# DM3370_Connector_C.net
KiCad netlist of a schematic drawn in Altium Designer
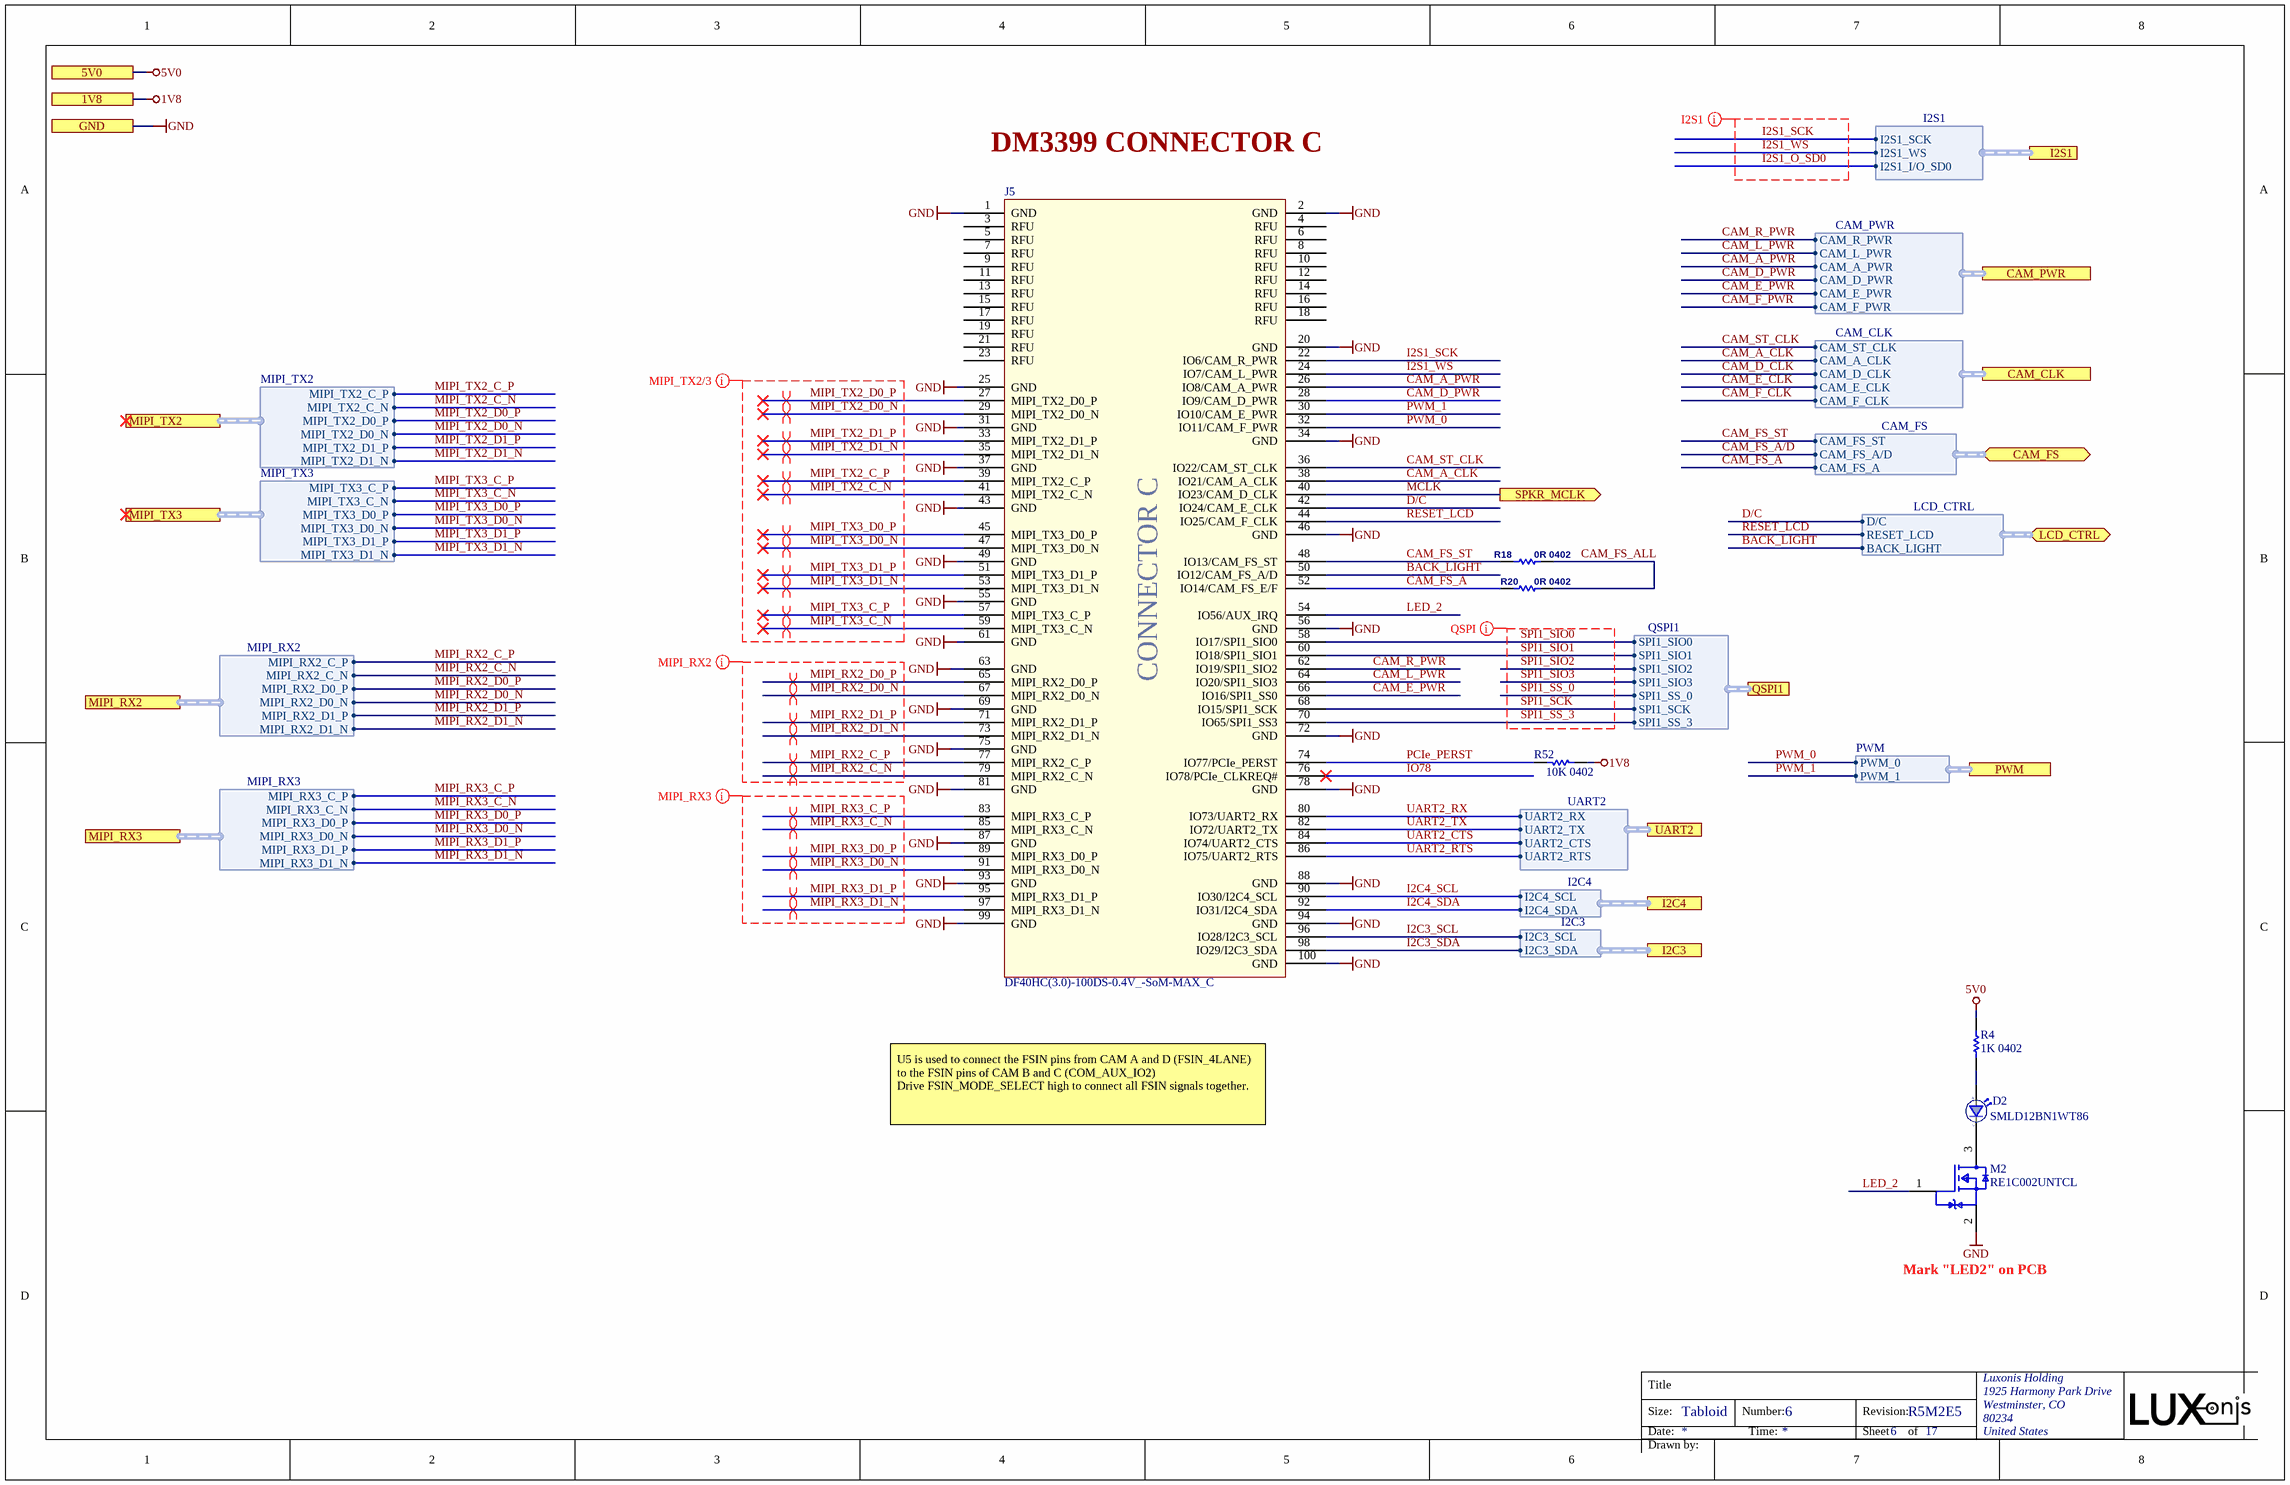
[diagram p0: DM3370_Connector_C.SchDoc]

(export (version "E")
  (design (tool "Eeschema 10.0.6"))
  (components
    (comp (ref "D2")
      (value "CMP-008-000009-2")
      (footprint "SML_D1xx8W")
      (description "LED Uni-Color Blue 2-Pin Chip 0603(1608Metric) T/R")
      (fields (field (name "MANUFACTURER PART NUMBER 1") "SMLD12BN1WT86"))
      (libsource (lib "Luxonis LLC") (part "SML-D12BN1WT86"))
    )
    (comp (ref "J5")
      (value "DF40HC(3.0)-100DS-0.4V_-SoM-MAX_C")
      (footprint "SOM_MAX_CONN_C_DF40HC-3.0-100DS-0.4V_minpad")
      (description "OAK-SoM-MAX base board conn. C")
      (fields (field (name "SOURCE") "LuxonisMaster_nejc.SchLib"))
      (libsource (lib "Luxonis LLC") (part "DF40HC(3.0)-100DS-0.4V_-SoM-MAX_C"))
    )
    (comp (ref "M2")
      (value "RE1C002UNTCL")
      (footprint "LuxonisMaster:RE1C002UNTCL")
      (description "MOSFET N-CH 20V 0.2A EMT3")
      (libsource (lib "LuxonisMaster") (part "RE1C002UNTCL"))
    )
    (comp (ref "R4")
      (value "1K 0402")
      (footprint "RES_Altium_Vault_Generic:RESC0402(1005)_L")
      (fields (field (name "TOLERANCE") "1%"))
      (libsource (lib "LuxonisMaster") (part "RC0402FR-071KL"))
    )
    (comp (ref "R18")
      (value "0R 0402")
      (footprint "RES_Altium_Vault_Generic:RESC0402(1005)_L")
      (description "RES SMD 0 OHM JUMPER 1/16W 0402")
      (fields (field (name "TOLERANCE") "5%"))
      (libsource (lib "LuxonisMaster") (part "CRCW04020000Z0ED"))
    )
    (comp (ref "R20")
      (value "0R 0402")
      (footprint "RES_Altium_Vault_Generic:RESC0402(1005)_L")
      (description "RES SMD 0 OHM JUMPER 1/16W 0402")
      (fields (field (name "TOLERANCE") "5%"))
      (libsource (lib "LuxonisMaster") (part "CRCW04020000Z0ED"))
    )
    (comp (ref "R52")
      (value "10K 0402")
      (footprint "RES_Altium_Vault_Generic:RESC0402(1005)_L")
      (fields (field (name "TOLERANCE") "1%"))
      (libsource (lib "LuxonisMaster") (part "RC0402FR-1310KL"))
    )
  )
  (nets
    (net (code "15") (name "/BACK_LIGHT") (class "Default")
      (node (ref "J5") (pin "50") (pinfunction "IO12/CAM_FS_A/D_50") (pintype "passive"))
    )
    (net (code "16") (name "/CAM_A_CLK") (class "Default")
      (node (ref "J5") (pin "38") (pinfunction "IO21/CAM_A_CLK_38") (pintype "passive"))
    )
    (net (code "17") (name "/CAM_A_PWR") (class "Default")
      (node (ref "J5") (pin "26") (pinfunction "IO8/CAM_A_PWR_26") (pintype "passive"))
    )
    (net (code "19") (name "/CAM_D_PWR") (class "Default")
      (node (ref "J5") (pin "28") (pinfunction "IO9/CAM_D_PWR_28") (pintype "passive"))
    )
    (net (code "21") (name "/CAM_E_PWR") (class "Default")
      (node (ref "J5") (pin "66") (pinfunction "IO16/SPI1_SS0_66") (pintype "passive"))
    )
    (net (code "22") (name "/CAM_FS_A") (class "Default")
      (node (ref "J5") (pin "52") (pinfunction "IO14/CAM_FS_E/F_52") (pintype "passive"))
      (node (ref "R20") (pin "2") (pinfunction "2_2") (pintype "passive"))
    )
    (net (code "23") (name "/CAM_FS_ALL") (class "Default")
      (node (ref "R18") (pin "1") (pinfunction "1_1") (pintype "passive"))
      (node (ref "R20") (pin "1") (pinfunction "1_1") (pintype "passive"))
    )
    (net (code "25") (name "/CAM_FS_ST") (class "Default")
      (node (ref "J5") (pin "48") (pinfunction "IO13/CAM_FS_ST_48") (pintype "passive"))
      (node (ref "R18") (pin "2") (pinfunction "2_2") (pintype "passive"))
    )
    (net (code "28") (name "/CAM_L_PWR") (class "Default")
      (node (ref "J5") (pin "64") (pinfunction "IO20/SPI1_SIO3_64") (pintype "passive"))
    )
    (net (code "29") (name "/CAM_R_PWR") (class "Default")
      (node (ref "J5") (pin "62") (pinfunction "IO19/SPI1_SIO2_62") (pintype "passive"))
    )
    (net (code "30") (name "/CAM_ST_CLK") (class "Default")
      (node (ref "J5") (pin "36") (pinfunction "IO22/CAM_ST_CLK_36") (pintype "passive"))
    )
    (net (code "31") (name "/D{slash}C") (class "Default")
      (node (ref "J5") (pin "42") (pinfunction "IO24/CAM_E_CLK_42") (pintype "passive"))
    )
    (net (code "32") (name "/I2C3_SCL") (class "Default")
      (node (ref "J5") (pin "96") (pinfunction "IO28/I2C3_SCL_96") (pintype "passive"))
    )
    (net (code "33") (name "/I2C3_SDA") (class "Default")
      (node (ref "J5") (pin "98") (pinfunction "IO29/I2C3_SDA_98") (pintype "passive"))
    )
    (net (code "34") (name "/I2C4_SCL") (class "Default")
      (node (ref "J5") (pin "90") (pinfunction "IO30/I2C4_SCL_90") (pintype "passive"))
    )
    (net (code "35") (name "/I2C4_SDA") (class "Default")
      (node (ref "J5") (pin "92") (pinfunction "IO31/I2C4_SDA_92") (pintype "passive"))
    )
    (net (code "37") (name "/I2S1_SCK") (class "Default")
      (node (ref "J5") (pin "22") (pinfunction "IO6/CAM_R_PWR_22") (pintype "passive"))
    )
    (net (code "38") (name "/I2S1_WS") (class "Default")
      (node (ref "J5") (pin "24") (pinfunction "IO7/CAM_L_PWR_24") (pintype "passive"))
    )
    (net (code "39") (name "/IO78") (class "Default")
      (node (ref "J5") (pin "76") (pinfunction "IO78/PCIe_CLKREQ#_76") (pintype "passive+no_connect"))
    )
    (net (code "40") (name "/LED_2") (class "Default")
      (node (ref "J5") (pin "54") (pinfunction "IO56/AUX_IRQ_54") (pintype "passive"))
      (node (ref "M2") (pin "1") (pinfunction "Gate_1") (pintype "passive"))
    )
    (net (code "41") (name "/MCLK") (class "Default")
      (node (ref "J5") (pin "40") (pinfunction "IO23/CAM_D_CLK_40") (pintype "passive"))
    )
    (net (code "42") (name "/MIPI_RX2_C_N") (class "Default")
      (node (ref "J5") (pin "79") (pinfunction "MIPI_RX2_C_N_79") (pintype "passive"))
    )
    (net (code "43") (name "/MIPI_RX2_C_P") (class "Default")
      (node (ref "J5") (pin "77") (pinfunction "MIPI_RX2_C_P_77") (pintype "passive"))
    )
    (net (code "44") (name "/MIPI_RX2_D0_N") (class "Default")
      (node (ref "J5") (pin "67") (pinfunction "MIPI_RX2_D0_N_67") (pintype "passive"))
    )
    (net (code "45") (name "/MIPI_RX2_D0_P") (class "Default")
      (node (ref "J5") (pin "65") (pinfunction "MIPI_RX2_D0_P_65") (pintype "passive"))
    )
    (net (code "46") (name "/MIPI_RX2_D1_N") (class "Default")
      (node (ref "J5") (pin "73") (pinfunction "MIPI_RX2_D1_N_73") (pintype "passive"))
    )
    (net (code "47") (name "/MIPI_RX2_D1_P") (class "Default")
      (node (ref "J5") (pin "71") (pinfunction "MIPI_RX2_D1_P_71") (pintype "passive"))
    )
    (net (code "48") (name "/MIPI_RX3_C_N") (class "Default")
      (node (ref "J5") (pin "85") (pinfunction "MIPI_RX3_C_N_85") (pintype "passive"))
    )
    (net (code "49") (name "/MIPI_RX3_C_P") (class "Default")
      (node (ref "J5") (pin "83") (pinfunction "MIPI_RX3_C_P_83") (pintype "passive"))
    )
    (net (code "50") (name "/MIPI_RX3_D0_N") (class "Default")
      (node (ref "J5") (pin "91") (pinfunction "MIPI_RX3_D0_N_91") (pintype "passive"))
    )
    (net (code "51") (name "/MIPI_RX3_D0_P") (class "Default")
      (node (ref "J5") (pin "89") (pinfunction "MIPI_RX3_D0_P_89") (pintype "passive"))
    )
    (net (code "52") (name "/MIPI_RX3_D1_N") (class "Default")
      (node (ref "J5") (pin "97") (pinfunction "MIPI_RX3_D1_N_97") (pintype "passive"))
    )
    (net (code "53") (name "/MIPI_RX3_D1_P") (class "Default")
      (node (ref "J5") (pin "95") (pinfunction "MIPI_RX3_D1_P_95") (pintype "passive"))
    )
    (net (code "54") (name "/MIPI_TX2_C_N") (class "Default")
      (node (ref "J5") (pin "41") (pinfunction "MIPI_TX2_C_N_41") (pintype "passive+no_connect"))
    )
    (net (code "55") (name "/MIPI_TX2_C_P") (class "Default")
      (node (ref "J5") (pin "39") (pinfunction "MIPI_TX2_C_P_39") (pintype "passive+no_connect"))
    )
    (net (code "56") (name "/MIPI_TX2_D0_N") (class "Default")
      (node (ref "J5") (pin "29") (pinfunction "MIPI_TX2_D0_N_29") (pintype "passive+no_connect"))
    )
    (net (code "57") (name "/MIPI_TX2_D0_P") (class "Default")
      (node (ref "J5") (pin "27") (pinfunction "MIPI_TX2_D0_P_27") (pintype "passive"))
    )
    (net (code "58") (name "/MIPI_TX2_D1_N") (class "Default")
      (node (ref "J5") (pin "35") (pinfunction "MIPI_TX2_D1_N_35") (pintype "passive"))
    )
    (net (code "59") (name "/MIPI_TX2_D1_P") (class "Default")
      (node (ref "J5") (pin "33") (pinfunction "MIPI_TX2_D1_P_33") (pintype "passive"))
    )
    (net (code "60") (name "/MIPI_TX3_C_N") (class "Default")
      (node (ref "J5") (pin "59") (pinfunction "MIPI_TX3_C_N_59") (pintype "passive"))
    )
    (net (code "61") (name "/MIPI_TX3_C_P") (class "Default")
      (node (ref "J5") (pin "57") (pinfunction "MIPI_TX3_C_P_57") (pintype "passive"))
    )
    (net (code "62") (name "/MIPI_TX3_D0_N") (class "Default")
      (node (ref "J5") (pin "47") (pinfunction "MIPI_TX3_D0_N_47") (pintype "passive"))
    )
    (net (code "63") (name "/MIPI_TX3_D0_P") (class "Default")
      (node (ref "J5") (pin "45") (pinfunction "MIPI_TX3_D0_P_45") (pintype "passive"))
    )
    (net (code "64") (name "/MIPI_TX3_D1_N") (class "Default")
      (node (ref "J5") (pin "53") (pinfunction "MIPI_TX3_D1_N_53") (pintype "passive"))
    )
    (net (code "65") (name "/MIPI_TX3_D1_P") (class "Default")
      (node (ref "J5") (pin "51") (pinfunction "MIPI_TX3_D1_P_51") (pintype "passive"))
    )
    (net (code "66") (name "/PCIe_PERST") (class "Default")
      (node (ref "J5") (pin "74") (pinfunction "IO77/PCIe_PERST_74") (pintype "passive"))
      (node (ref "R52") (pin "2") (pinfunction "2_2") (pintype "passive"))
    )
    (net (code "67") (name "/PWM_0") (class "Default")
      (node (ref "J5") (pin "32") (pinfunction "IO11/CAM_F_PWR_32") (pintype "passive"))
    )
    (net (code "68") (name "/PWM_1") (class "Default")
      (node (ref "J5") (pin "30") (pinfunction "IO10/CAM_E_PWR_30") (pintype "passive"))
    )
    (net (code "69") (name "/RESET_LCD") (class "Default")
      (node (ref "J5") (pin "44") (pinfunction "IO25/CAM_F_CLK_44") (pintype "passive"))
    )
    (net (code "70") (name "/SPI1_SCK") (class "Default")
      (node (ref "J5") (pin "68") (pinfunction "IO15/SPI1_SCK_68") (pintype "passive"))
    )
    (net (code "71") (name "/SPI1_SIO0") (class "Default")
      (node (ref "J5") (pin "58") (pinfunction "IO17/SPI1_SIO0_58") (pintype "passive"))
    )
    (net (code "72") (name "/SPI1_SIO1") (class "Default")
      (node (ref "J5") (pin "60") (pinfunction "IO18/SPI1_SIO1_60") (pintype "passive"))
    )
    (net (code "76") (name "/SPI1_SS_3") (class "Default")
      (node (ref "J5") (pin "70") (pinfunction "IO65/SPI1_SS3_70") (pintype "passive"))
    )
    (net (code "77") (name "/UART2_CTS") (class "Default")
      (node (ref "J5") (pin "84") (pinfunction "IO74/UART2_CTS_84") (pintype "passive"))
    )
    (net (code "78") (name "/UART2_RTS") (class "Default")
      (node (ref "J5") (pin "86") (pinfunction "IO75/UART2_RTS_86") (pintype "passive"))
    )
    (net (code "79") (name "/UART2_RX") (class "Default")
      (node (ref "J5") (pin "80") (pinfunction "IO73/UART2_RX_80") (pintype "passive"))
    )
    (net (code "80") (name "/UART2_TX") (class "Default")
      (node (ref "J5") (pin "82") (pinfunction "IO72/UART2_TX_82") (pintype "passive"))
    )
    (net (code "95") (name "1V8") (class "Default")
      (node (ref "R52") (pin "1") (pinfunction "1_1") (pintype "passive"))
    )
    (net (code "96") (name "5V0") (class "Default")
      (node (ref "R4") (pin "2") (pinfunction "2_2") (pintype "passive"))
    )
    (net (code "97") (name "GND") (class "Default")
      (node (ref "J5") (pin "1") (pinfunction "GND_1") (pintype "passive"))
      (node (ref "J5") (pin "100") (pinfunction "GND_100") (pintype "passive"))
      (node (ref "J5") (pin "2") (pinfunction "GND_2") (pintype "passive"))
      (node (ref "J5") (pin "20") (pinfunction "GND_20") (pintype "passive"))
      (node (ref "J5") (pin "25") (pinfunction "GND_25") (pintype "passive"))
      (node (ref "J5") (pin "31") (pinfunction "GND_31") (pintype "passive"))
      (node (ref "J5") (pin "34") (pinfunction "GND_34") (pintype "passive"))
      (node (ref "J5") (pin "37") (pinfunction "GND_37") (pintype "passive"))
      (node (ref "J5") (pin "43") (pinfunction "GND_43") (pintype "passive"))
      (node (ref "J5") (pin "46") (pinfunction "GND_46") (pintype "passive"))
      (node (ref "J5") (pin "49") (pinfunction "GND_49") (pintype "passive"))
      (node (ref "J5") (pin "55") (pinfunction "GND_55") (pintype "passive"))
      (node (ref "J5") (pin "56") (pinfunction "GND_56") (pintype "passive"))
      (node (ref "J5") (pin "61") (pinfunction "GND_61") (pintype "passive"))
      (node (ref "J5") (pin "63") (pinfunction "GND_63") (pintype "passive"))
      (node (ref "J5") (pin "69") (pinfunction "GND_69") (pintype "passive"))
      (node (ref "J5") (pin "72") (pinfunction "GND_72") (pintype "passive"))
      (node (ref "J5") (pin "75") (pinfunction "GND_75") (pintype "passive"))
      (node (ref "J5") (pin "78") (pinfunction "GND_78") (pintype "passive"))
      (node (ref "J5") (pin "81") (pinfunction "GND_81") (pintype "passive"))
      (node (ref "J5") (pin "87") (pinfunction "GND_87") (pintype "passive"))
      (node (ref "J5") (pin "88") (pinfunction "GND_88") (pintype "passive"))
      (node (ref "J5") (pin "93") (pinfunction "GND_93") (pintype "passive"))
      (node (ref "J5") (pin "94") (pinfunction "GND_94") (pintype "passive"))
      (node (ref "J5") (pin "99") (pinfunction "GND_99") (pintype "passive"))
      (node (ref "M2") (pin "2") (pinfunction "Source_2") (pintype "passive"))
    )
    (net (code "98") (name "Net-(D2-A)") (class "Default")
      (node (ref "D2") (pin "2") (pinfunction "A_2") (pintype "passive"))
      (node (ref "R4") (pin "1") (pinfunction "1_1") (pintype "passive"))
    )
    (net (code "99") (name "Net-(D2-C)") (class "Default")
      (node (ref "D2") (pin "1") (pinfunction "C_1") (pintype "passive"))
      (node (ref "M2") (pin "3") (pinfunction "Drain_3") (pintype "passive"))
    )
    (net (code "100") (name "unconnected-(J5-RFU-Pad3)") (class "Default")
      (node (ref "J5") (pin "3") (pinfunction "RFU_3") (pintype "passive"))
    )
    (net (code "101") (name "unconnected-(J5-RFU-Pad4)") (class "Default")
      (node (ref "J5") (pin "4") (pinfunction "RFU_4") (pintype "passive"))
    )
    (net (code "102") (name "unconnected-(J5-RFU-Pad5)") (class "Default")
      (node (ref "J5") (pin "5") (pinfunction "RFU_5") (pintype "passive"))
    )
    (net (code "103") (name "unconnected-(J5-RFU-Pad6)") (class "Default")
      (node (ref "J5") (pin "6") (pinfunction "RFU_6") (pintype "passive"))
    )
    (net (code "104") (name "unconnected-(J5-RFU-Pad7)") (class "Default")
      (node (ref "J5") (pin "7") (pinfunction "RFU_7") (pintype "passive"))
    )
    (net (code "105") (name "unconnected-(J5-RFU-Pad8)") (class "Default")
      (node (ref "J5") (pin "8") (pinfunction "RFU_8") (pintype "passive"))
    )
    (net (code "106") (name "unconnected-(J5-RFU-Pad9)") (class "Default")
      (node (ref "J5") (pin "9") (pinfunction "RFU_9") (pintype "passive"))
    )
    (net (code "107") (name "unconnected-(J5-RFU-Pad10)") (class "Default")
      (node (ref "J5") (pin "10") (pinfunction "RFU_10") (pintype "passive"))
    )
    (net (code "108") (name "unconnected-(J5-RFU-Pad11)") (class "Default")
      (node (ref "J5") (pin "11") (pinfunction "RFU_11") (pintype "passive"))
    )
    (net (code "109") (name "unconnected-(J5-RFU-Pad12)") (class "Default")
      (node (ref "J5") (pin "12") (pinfunction "RFU_12") (pintype "passive"))
    )
    (net (code "110") (name "unconnected-(J5-RFU-Pad13)") (class "Default")
      (node (ref "J5") (pin "13") (pinfunction "RFU_13") (pintype "passive"))
    )
    (net (code "111") (name "unconnected-(J5-RFU-Pad14)") (class "Default")
      (node (ref "J5") (pin "14") (pinfunction "RFU_14") (pintype "passive"))
    )
    (net (code "112") (name "unconnected-(J5-RFU-Pad15)") (class "Default")
      (node (ref "J5") (pin "15") (pinfunction "RFU_15") (pintype "passive"))
    )
    (net (code "113") (name "unconnected-(J5-RFU-Pad16)") (class "Default")
      (node (ref "J5") (pin "16") (pinfunction "RFU_16") (pintype "passive"))
    )
    (net (code "114") (name "unconnected-(J5-RFU-Pad17)") (class "Default")
      (node (ref "J5") (pin "17") (pinfunction "RFU_17") (pintype "passive"))
    )
    (net (code "115") (name "unconnected-(J5-RFU-Pad18)") (class "Default")
      (node (ref "J5") (pin "18") (pinfunction "RFU_18") (pintype "passive"))
    )
    (net (code "116") (name "unconnected-(J5-RFU-Pad19)") (class "Default")
      (node (ref "J5") (pin "19") (pinfunction "RFU_19") (pintype "passive"))
    )
    (net (code "117") (name "unconnected-(J5-RFU-Pad21)") (class "Default")
      (node (ref "J5") (pin "21") (pinfunction "RFU_21") (pintype "passive"))
    )
    (net (code "118") (name "unconnected-(J5-RFU-Pad23)") (class "Default")
      (node (ref "J5") (pin "23") (pinfunction "RFU_23") (pintype "passive"))
    )
  )
)
